# Arduino.net
KiCad netlist of a schematic drawn in Altium Designer
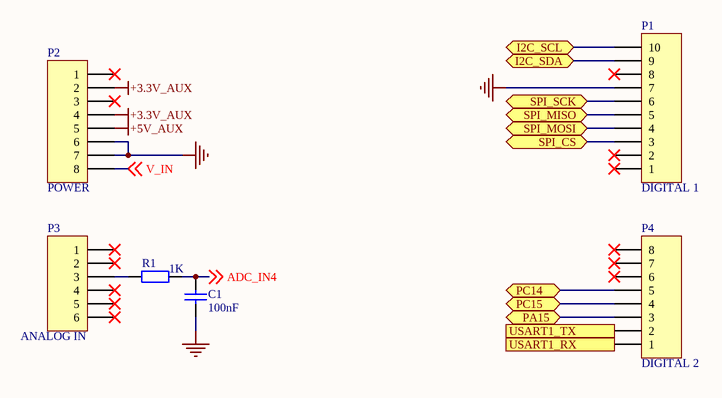
[diagram p0: Arduino.SchDoc]

(export (version "E")
  (design (tool "Eeschema 10.0.6"))
  (components
    (comp (ref "C1")
      (value "100nF")
      (footprint "C0402")
      (description "Capacitor ceramic")
      (fields
        (field (name "MANUFACTURER") "TDK Corporation")
        (field (name "MANUFACTURER PART NO.") "CGA2B3X7R1V104K050BB")
      )
      (libsource (lib "Miscellaneous Devices") (part "Cap"))
    )
    (comp (ref "P1")
      (value "DIGITAL 1")
      (footprint "HDR1X10")
      (fields
        (field (name "MANUFACTURER") "SparkFun Electronics")
        (field (name "MANUFACTURER PART NO.") "PRT-11417")
      )
      (libsource (lib "Miscellaneous Connectors") (part "Header 10"))
    )
    (comp (ref "P2")
      (value "POWER")
      (footprint "HDR1X8")
      (fields (field (name "MANUFACTURER") "ADAM TECH") (field (name "MANUFACTURER PART NO.") "RS1-08-G"))
      (libsource (lib "") (part "Header 8_1"))
    )
    (comp (ref "P3")
      (value "ANALOG IN")
      (footprint "HDR1X6")
      (fields (field (name "MANUFACTURER") "ADAM TECH") (field (name "MANUFACTURER PART NO.") "RS1-06-G"))
      (libsource (lib "Miscellaneous Connectors") (part "Header 6"))
    )
    (comp (ref "P4")
      (value "DIGITAL 2")
      (footprint "HDR1X8")
      (fields (field (name "MANUFACTURER") "ADAM TECH") (field (name "MANUFACTURER PART NO.") "RS1-08-G"))
      (libsource (lib "Miscellaneous Connectors") (part "Header 8"))
    )
    (comp (ref "R1")
      (value "1K")
      (footprint "R0402")
      (description "Resistor")
      (fields (field (name "MANUFACTURER") "Yageo") (field (name "MANUFACTURER PART NO.") "AC0402JR-071KL"))
      (libsource (lib "Miscellaneous Devices") (part "Res2"))
    )
  )
  (nets
    (net (code "1") (name "+3.3V_AUX") (class "Default")
      (node (ref "P2") (pin "2") (pinfunction "2_2") (pintype "passive"))
      (node (ref "P2") (pin "4") (pinfunction "4_4") (pintype "passive"))
    )
    (net (code "2") (name "+5V_AUX") (class "Default")
      (node (ref "P2") (pin "5") (pinfunction "5_5") (pintype "passive"))
    )
    (net (code "3") (name "/I2C_SCL") (class "Default")
      (node (ref "P1") (pin "10") (pinfunction "10_10") (pintype "passive"))
    )
    (net (code "4") (name "/I2C_SDA") (class "Default")
      (node (ref "P1") (pin "9") (pinfunction "9_9") (pintype "passive"))
    )
    (net (code "5") (name "/PA15") (class "Default")
      (node (ref "P4") (pin "3") (pinfunction "3_3") (pintype "passive"))
    )
    (net (code "6") (name "/PC14") (class "Default")
      (node (ref "P4") (pin "5") (pinfunction "5_5") (pintype "passive"))
    )
    (net (code "7") (name "/PC15") (class "Default")
      (node (ref "P4") (pin "4") (pinfunction "4_4") (pintype "passive"))
    )
    (net (code "8") (name "/SPI_CS") (class "Default")
      (node (ref "P1") (pin "3") (pinfunction "3_3") (pintype "passive"))
    )
    (net (code "9") (name "/SPI_MISO") (class "Default")
      (node (ref "P1") (pin "5") (pinfunction "5_5") (pintype "passive"))
    )
    (net (code "10") (name "/SPI_MOSI") (class "Default")
      (node (ref "P1") (pin "4") (pinfunction "4_4") (pintype "passive"))
    )
    (net (code "11") (name "/SPI_SCK") (class "Default")
      (node (ref "P1") (pin "6") (pinfunction "6_6") (pintype "passive"))
    )
    (net (code "12") (name "/USART1_RX") (class "Default")
      (node (ref "P4") (pin "1") (pinfunction "1_1") (pintype "passive"))
    )
    (net (code "13") (name "/USART1_TX") (class "Default")
      (node (ref "P4") (pin "2") (pinfunction "2_2") (pintype "passive"))
    )
    (net (code "14") (name "ADC_IN4") (class "Default")
      (node (ref "C1") (pin "1") (pinfunction "1_1") (pintype "passive"))
      (node (ref "R1") (pin "2") (pinfunction "2_2") (pintype "passive"))
    )
    (net (code "15") (name "GND") (class "Default")
      (node (ref "C1") (pin "2") (pinfunction "2_2") (pintype "passive"))
      (node (ref "P1") (pin "7") (pinfunction "7_7") (pintype "passive"))
      (node (ref "P2") (pin "6") (pinfunction "6_6") (pintype "passive"))
      (node (ref "P2") (pin "7") (pinfunction "7_7") (pintype "passive"))
    )
    (net (code "16") (name "Net-(P3-Pad3)") (class "Default")
      (node (ref "P3") (pin "3") (pinfunction "3_3") (pintype "passive"))
      (node (ref "R1") (pin "1") (pinfunction "1_1") (pintype "passive"))
    )
    (net (code "17") (name "V_IN") (class "Default")
      (node (ref "P2") (pin "8") (pinfunction "8_8") (pintype "passive"))
    )
    (net (code "18") (name "unconnected-(P1-Pad1)") (class "Default")
      (node (ref "P1") (pin "1") (pinfunction "1_1") (pintype "passive+no_connect"))
    )
    (net (code "19") (name "unconnected-(P1-Pad2)") (class "Default")
      (node (ref "P1") (pin "2") (pinfunction "2_2") (pintype "passive+no_connect"))
    )
    (net (code "20") (name "unconnected-(P1-Pad8)") (class "Default")
      (node (ref "P1") (pin "8") (pinfunction "8_8") (pintype "passive+no_connect"))
    )
    (net (code "21") (name "unconnected-(P2-Pad1)") (class "Default")
      (node (ref "P2") (pin "1") (pinfunction "1_1") (pintype "passive+no_connect"))
    )
    (net (code "22") (name "unconnected-(P2-Pad3)") (class "Default")
      (node (ref "P2") (pin "3") (pinfunction "3_3") (pintype "passive+no_connect"))
    )
    (net (code "23") (name "unconnected-(P3-Pad1)") (class "Default")
      (node (ref "P3") (pin "1") (pinfunction "1_1") (pintype "passive+no_connect"))
    )
    (net (code "24") (name "unconnected-(P3-Pad2)") (class "Default")
      (node (ref "P3") (pin "2") (pinfunction "2_2") (pintype "passive+no_connect"))
    )
    (net (code "25") (name "unconnected-(P3-Pad4)") (class "Default")
      (node (ref "P3") (pin "4") (pinfunction "4_4") (pintype "passive+no_connect"))
    )
    (net (code "26") (name "unconnected-(P3-Pad5)") (class "Default")
      (node (ref "P3") (pin "5") (pinfunction "5_5") (pintype "passive+no_connect"))
    )
    (net (code "27") (name "unconnected-(P3-Pad6)") (class "Default")
      (node (ref "P3") (pin "6") (pinfunction "6_6") (pintype "passive+no_connect"))
    )
    (net (code "28") (name "unconnected-(P4-Pad6)") (class "Default")
      (node (ref "P4") (pin "6") (pinfunction "6_6") (pintype "passive+no_connect"))
    )
    (net (code "29") (name "unconnected-(P4-Pad7)") (class "Default")
      (node (ref "P4") (pin "7") (pinfunction "7_7") (pintype "passive+no_connect"))
    )
    (net (code "30") (name "unconnected-(P4-Pad8)") (class "Default")
      (node (ref "P4") (pin "8") (pinfunction "8_8") (pintype "passive+no_connect"))
    )
  )
)
